# Relay_Board_Rev1-2_-_EasyEDA.net
KiCad netlist of a schematic drawn in EasyEDA
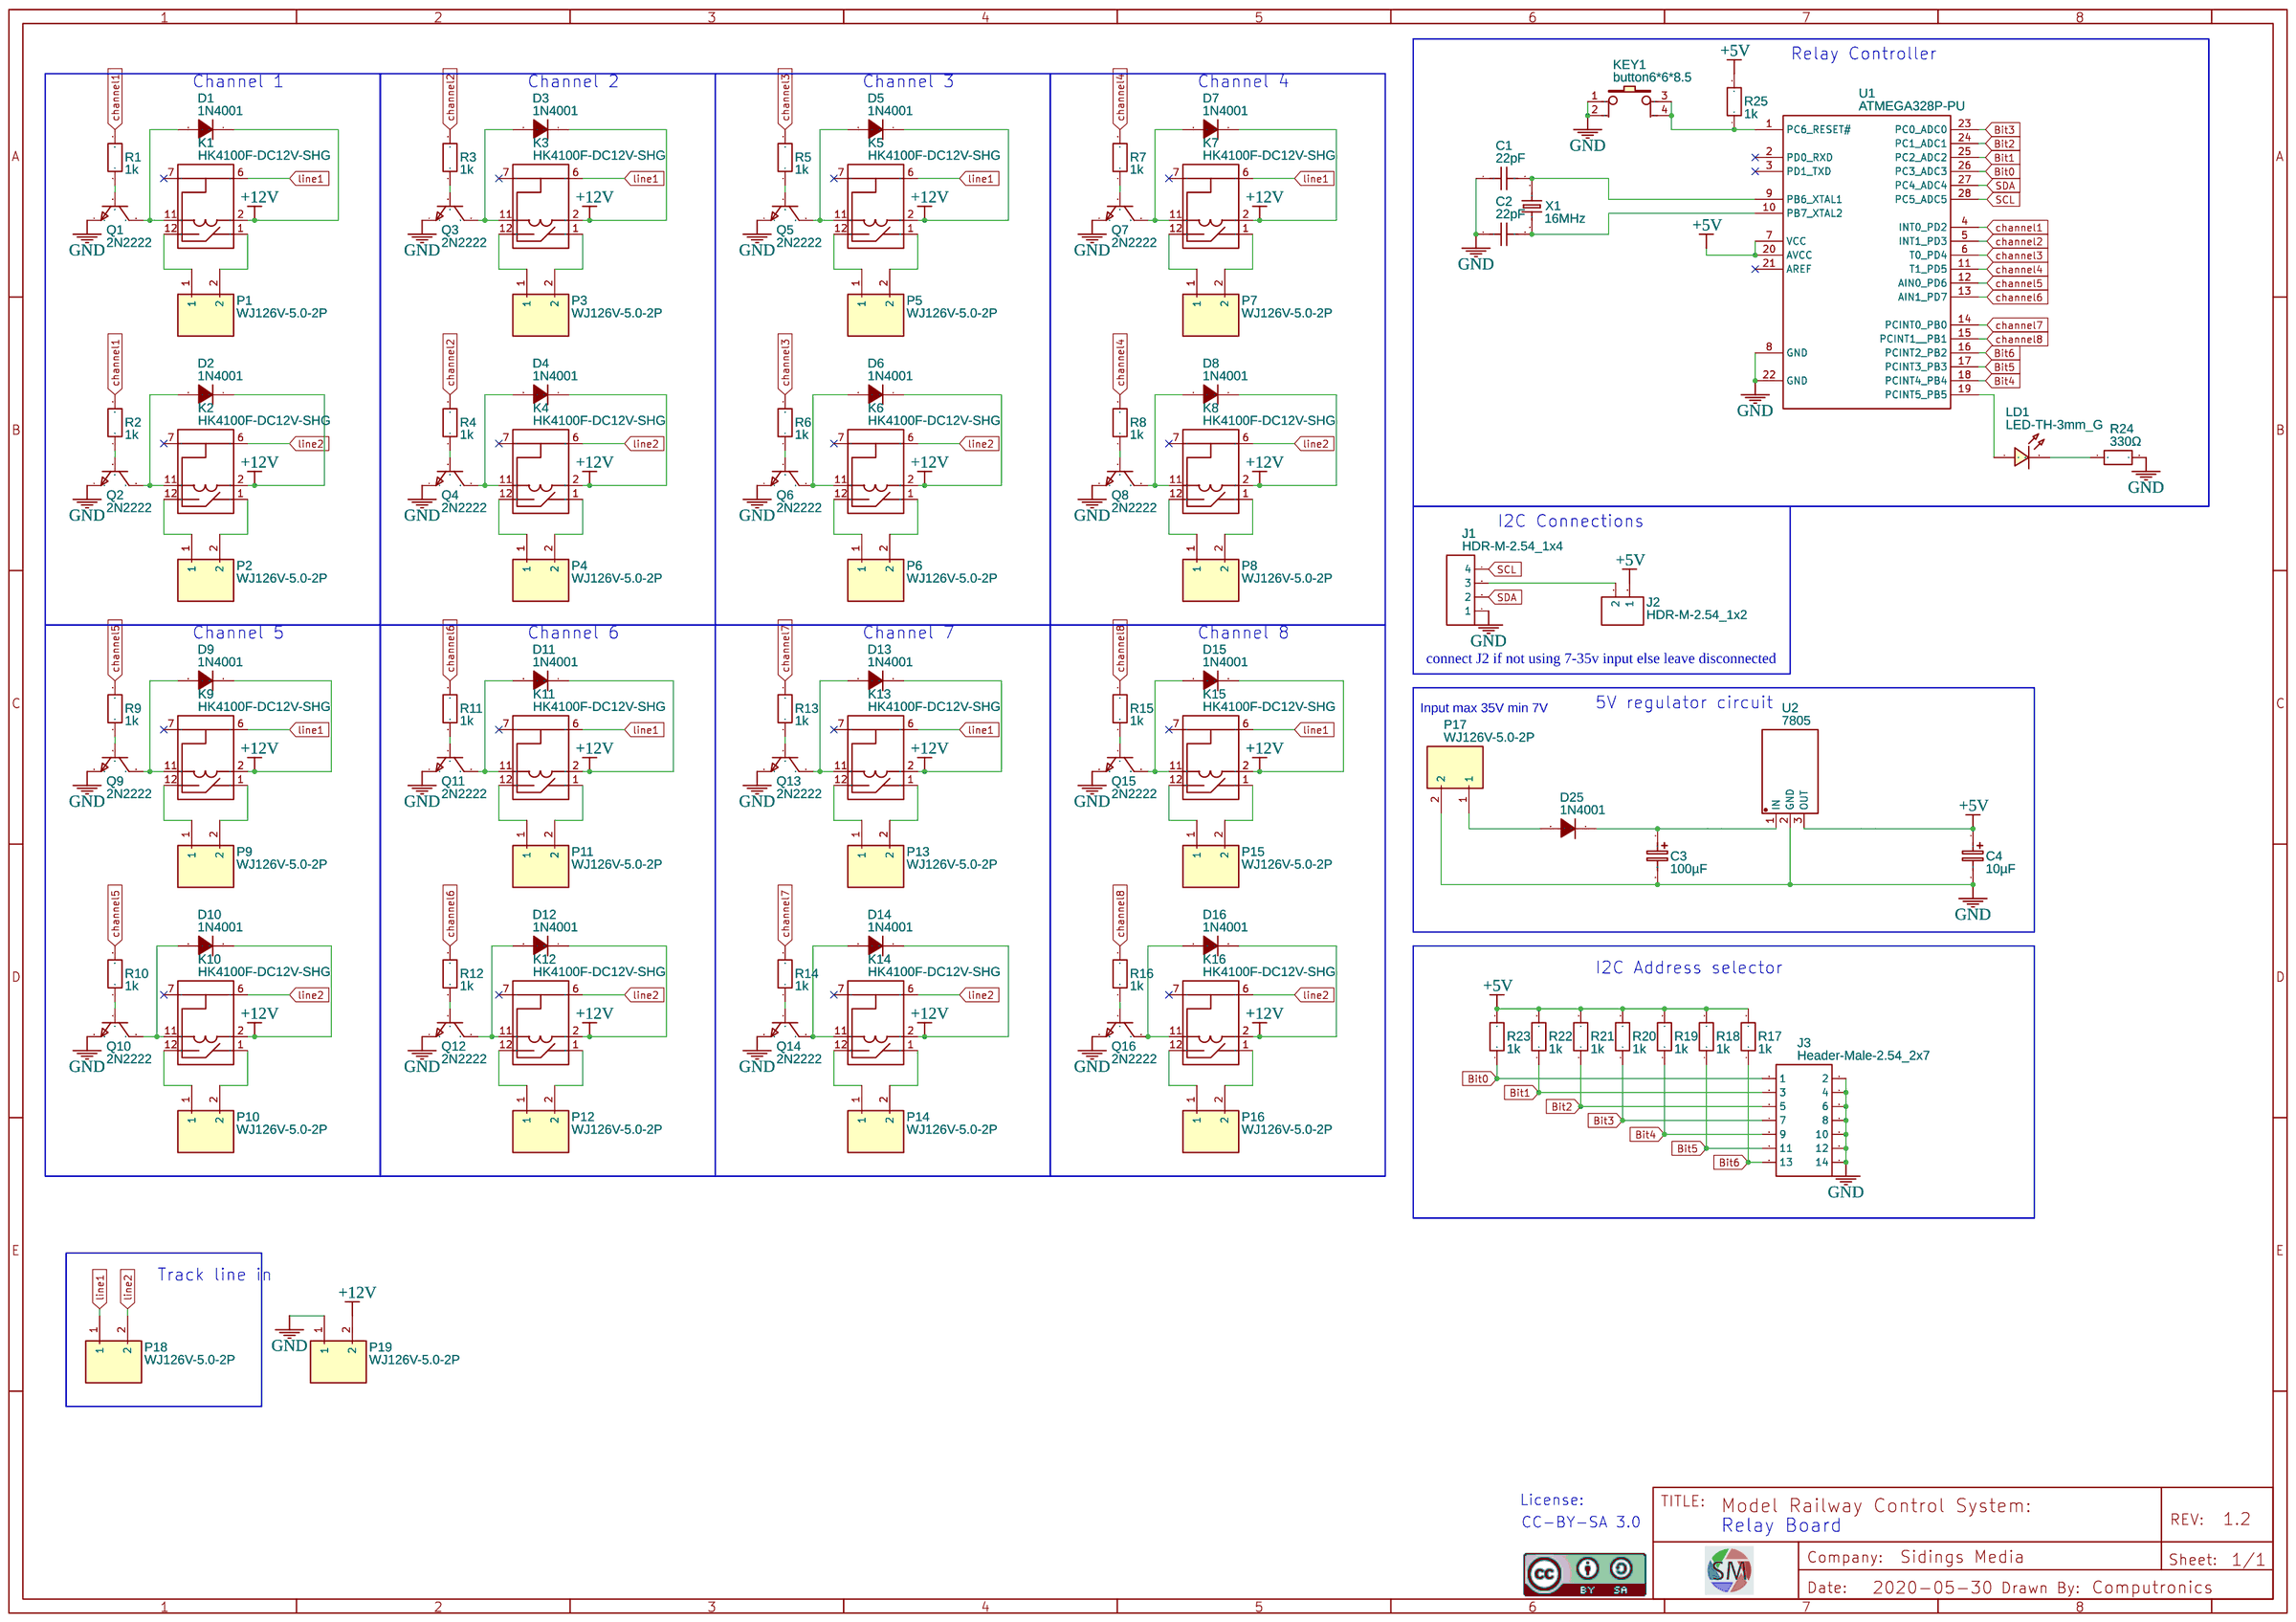
[diagram p0: schematic sheet]

(export (version "E")
  (design (tool "Eeschema 10.0.6"))
  (components
    (comp (ref "C1") (value "22pF") (libsource (lib "") (part "C_RAD-0.2_US")))
    (comp (ref "C2") (value "22pF") (libsource (lib "") (part "C_RAD-0.2_US")))
    (comp (ref "C3") (value "100µF") (libsource (lib "") (part "CE_TH_D3.0×F1.5_EU")))
    (comp (ref "C4") (value "10µF") (libsource (lib "") (part "CE_TH_D3.0×F1.5_EU")))
    (comp (ref "D1")
      (value "1N4001")
      (fields (field (name "BOM_Supplier Part") "C82804"))
      (libsource (lib "") (part "1N4001"))
    )
    (comp (ref "D2")
      (value "1N4001")
      (fields (field (name "BOM_Supplier Part") "C82804"))
      (libsource (lib "") (part "1N4001"))
    )
    (comp (ref "D3")
      (value "1N4001")
      (fields (field (name "BOM_Supplier Part") "C82804"))
      (libsource (lib "") (part "1N4001"))
    )
    (comp (ref "D4")
      (value "1N4001")
      (fields (field (name "BOM_Supplier Part") "C82804"))
      (libsource (lib "") (part "1N4001"))
    )
    (comp (ref "D5")
      (value "1N4001")
      (fields (field (name "BOM_Supplier Part") "C82804"))
      (libsource (lib "") (part "1N4001"))
    )
    (comp (ref "D6")
      (value "1N4001")
      (fields (field (name "BOM_Supplier Part") "C82804"))
      (libsource (lib "") (part "1N4001"))
    )
    (comp (ref "D7")
      (value "1N4001")
      (fields (field (name "BOM_Supplier Part") "C82804"))
      (libsource (lib "") (part "1N4001"))
    )
    (comp (ref "D8")
      (value "1N4001")
      (fields (field (name "BOM_Supplier Part") "C82804"))
      (libsource (lib "") (part "1N4001"))
    )
    (comp (ref "D9")
      (value "1N4001")
      (fields (field (name "BOM_Supplier Part") "C82804"))
      (libsource (lib "") (part "1N4001"))
    )
    (comp (ref "D10")
      (value "1N4001")
      (fields (field (name "BOM_Supplier Part") "C82804"))
      (libsource (lib "") (part "1N4001"))
    )
    (comp (ref "D11")
      (value "1N4001")
      (fields (field (name "BOM_Supplier Part") "C82804"))
      (libsource (lib "") (part "1N4001"))
    )
    (comp (ref "D12")
      (value "1N4001")
      (fields (field (name "BOM_Supplier Part") "C82804"))
      (libsource (lib "") (part "1N4001"))
    )
    (comp (ref "D13")
      (value "1N4001")
      (fields (field (name "BOM_Supplier Part") "C82804"))
      (libsource (lib "") (part "1N4001"))
    )
    (comp (ref "D14")
      (value "1N4001")
      (fields (field (name "BOM_Supplier Part") "C82804"))
      (libsource (lib "") (part "1N4001"))
    )
    (comp (ref "D15")
      (value "1N4001")
      (fields (field (name "BOM_Supplier Part") "C82804"))
      (libsource (lib "") (part "1N4001"))
    )
    (comp (ref "D16")
      (value "1N4001")
      (fields (field (name "BOM_Supplier Part") "C82804"))
      (libsource (lib "") (part "1N4001"))
    )
    (comp (ref "D25")
      (value "1N4001")
      (fields (field (name "BOM_Supplier Part") "C82804"))
      (libsource (lib "") (part "1N4001"))
    )
    (comp (ref "J1")
      (value "HDR-M-2.54_1x4")
      (fields (field (name "BOM_Supplier Part") "C124378"))
      (libsource (lib "") (part "HDR-M-2.54_1x4"))
    )
    (comp (ref "J2")
      (value "HDR-M-2.54_1x2")
      (fields (field (name "BOM_Supplier Part") "C124375"))
      (libsource (lib "") (part "HDR-M-2.54_1x2"))
    )
    (comp (ref "J3")
      (value "Header-Male-2.54_2x7")
      (fields
        (field (name "BOM_Manufacturer Part") "Double row of needle2X7P 2.54mm")
        (field (name "BOM_Supplier Part") "C71397")
      )
      (libsource (lib "") (part "Header-Male-2.54_2x7"))
    )
    (comp (ref "K1")
      (value "HK4100F-DC12V-SHG")
      (fields (field (name "BOM_Supplier Part") "C13467"))
      (libsource (lib "") (part "HK4100F-DC12V-SHG_1"))
    )
    (comp (ref "K2")
      (value "HK4100F-DC12V-SHG")
      (fields (field (name "BOM_Supplier Part") "C13467"))
      (libsource (lib "") (part "HK4100F-DC12V-SHG_1"))
    )
    (comp (ref "K3")
      (value "HK4100F-DC12V-SHG")
      (fields (field (name "BOM_Supplier Part") "C13467"))
      (libsource (lib "") (part "HK4100F-DC12V-SHG"))
    )
    (comp (ref "K4")
      (value "HK4100F-DC12V-SHG")
      (fields (field (name "BOM_Supplier Part") "C13467"))
      (libsource (lib "") (part "HK4100F-DC12V-SHG"))
    )
    (comp (ref "K5")
      (value "HK4100F-DC12V-SHG")
      (fields (field (name "BOM_Supplier Part") "C13467"))
      (libsource (lib "") (part "HK4100F-DC12V-SHG"))
    )
    (comp (ref "K6")
      (value "HK4100F-DC12V-SHG")
      (fields (field (name "BOM_Supplier Part") "C13467"))
      (libsource (lib "") (part "HK4100F-DC12V-SHG"))
    )
    (comp (ref "K7")
      (value "HK4100F-DC12V-SHG")
      (fields (field (name "BOM_Supplier Part") "C13467"))
      (libsource (lib "") (part "HK4100F-DC12V-SHG"))
    )
    (comp (ref "K8")
      (value "HK4100F-DC12V-SHG")
      (fields (field (name "BOM_Supplier Part") "C13467"))
      (libsource (lib "") (part "HK4100F-DC12V-SHG"))
    )
    (comp (ref "K9")
      (value "HK4100F-DC12V-SHG")
      (fields (field (name "BOM_Supplier Part") "C13467"))
      (libsource (lib "") (part "HK4100F-DC12V-SHG_1"))
    )
    (comp (ref "K10")
      (value "HK4100F-DC12V-SHG")
      (fields (field (name "BOM_Supplier Part") "C13467"))
      (libsource (lib "") (part "HK4100F-DC12V-SHG_1"))
    )
    (comp (ref "K11")
      (value "HK4100F-DC12V-SHG")
      (fields (field (name "BOM_Supplier Part") "C13467"))
      (libsource (lib "") (part "HK4100F-DC12V-SHG"))
    )
    (comp (ref "K12")
      (value "HK4100F-DC12V-SHG")
      (fields (field (name "BOM_Supplier Part") "C13467"))
      (libsource (lib "") (part "HK4100F-DC12V-SHG"))
    )
    (comp (ref "K13")
      (value "HK4100F-DC12V-SHG")
      (fields (field (name "BOM_Supplier Part") "C13467"))
      (libsource (lib "") (part "HK4100F-DC12V-SHG"))
    )
    (comp (ref "K14")
      (value "HK4100F-DC12V-SHG")
      (fields (field (name "BOM_Supplier Part") "C13467"))
      (libsource (lib "") (part "HK4100F-DC12V-SHG"))
    )
    (comp (ref "K15")
      (value "HK4100F-DC12V-SHG")
      (fields (field (name "BOM_Supplier Part") "C13467"))
      (libsource (lib "") (part "HK4100F-DC12V-SHG"))
    )
    (comp (ref "K16")
      (value "HK4100F-DC12V-SHG")
      (fields (field (name "BOM_Supplier Part") "C13467"))
      (libsource (lib "") (part "HK4100F-DC12V-SHG"))
    )
    (comp (ref "KEY1")
      (value "button6*6*8.5")
      (fields (field (name "BOM_Supplier Part") "C59980"))
      (libsource (lib "") (part "button6*6*8.5"))
    )
    (comp (ref "LD1")
      (value "LED-TH-3mm_G")
      (fields
        (field (name "BOM_Manufacturer Part") "204-10SYGD/S530-E3")
        (field (name "BOM_Supplier Part") "C85161")
      )
      (libsource (lib "") (part "LED-TH-3mm_G"))
    )
    (comp (ref "P1")
      (value "WJ126V-5.0-2P")
      (fields (field (name "BOM_Supplier Part") "C8404"))
      (libsource (lib "") (part "WJ126V-5.0-2P"))
    )
    (comp (ref "P2")
      (value "WJ126V-5.0-2P")
      (fields (field (name "BOM_Supplier Part") "C8404"))
      (libsource (lib "") (part "WJ126V-5.0-2P"))
    )
    (comp (ref "P3")
      (value "WJ126V-5.0-2P")
      (fields (field (name "BOM_Supplier Part") "C8404"))
      (libsource (lib "") (part "WJ126V-5.0-2P"))
    )
    (comp (ref "P4")
      (value "WJ126V-5.0-2P")
      (fields (field (name "BOM_Supplier Part") "C8404"))
      (libsource (lib "") (part "WJ126V-5.0-2P"))
    )
    (comp (ref "P5")
      (value "WJ126V-5.0-2P")
      (fields (field (name "BOM_Supplier Part") "C8404"))
      (libsource (lib "") (part "WJ126V-5.0-2P"))
    )
    (comp (ref "P6")
      (value "WJ126V-5.0-2P")
      (fields (field (name "BOM_Supplier Part") "C8404"))
      (libsource (lib "") (part "WJ126V-5.0-2P"))
    )
    (comp (ref "P7")
      (value "WJ126V-5.0-2P")
      (fields (field (name "BOM_Supplier Part") "C8404"))
      (libsource (lib "") (part "WJ126V-5.0-2P"))
    )
    (comp (ref "P8")
      (value "WJ126V-5.0-2P")
      (fields (field (name "BOM_Supplier Part") "C8404"))
      (libsource (lib "") (part "WJ126V-5.0-2P"))
    )
    (comp (ref "P9")
      (value "WJ126V-5.0-2P")
      (fields (field (name "BOM_Supplier Part") "C8404"))
      (libsource (lib "") (part "WJ126V-5.0-2P"))
    )
    (comp (ref "P10")
      (value "WJ126V-5.0-2P")
      (fields (field (name "BOM_Supplier Part") "C8404"))
      (libsource (lib "") (part "WJ126V-5.0-2P"))
    )
    (comp (ref "P11")
      (value "WJ126V-5.0-2P")
      (fields (field (name "BOM_Supplier Part") "C8404"))
      (libsource (lib "") (part "WJ126V-5.0-2P"))
    )
    (comp (ref "P12")
      (value "WJ126V-5.0-2P")
      (fields (field (name "BOM_Supplier Part") "C8404"))
      (libsource (lib "") (part "WJ126V-5.0-2P"))
    )
    (comp (ref "P13")
      (value "WJ126V-5.0-2P")
      (fields (field (name "BOM_Supplier Part") "C8404"))
      (libsource (lib "") (part "WJ126V-5.0-2P"))
    )
    (comp (ref "P14")
      (value "WJ126V-5.0-2P")
      (fields (field (name "BOM_Supplier Part") "C8404"))
      (libsource (lib "") (part "WJ126V-5.0-2P"))
    )
    (comp (ref "P15")
      (value "WJ126V-5.0-2P")
      (fields (field (name "BOM_Supplier Part") "C8404"))
      (libsource (lib "") (part "WJ126V-5.0-2P"))
    )
    (comp (ref "P16")
      (value "WJ126V-5.0-2P")
      (fields (field (name "BOM_Supplier Part") "C8404"))
      (libsource (lib "") (part "WJ126V-5.0-2P"))
    )
    (comp (ref "P17")
      (value "WJ126V-5.0-2P")
      (fields (field (name "BOM_Supplier Part") "C8404"))
      (libsource (lib "") (part "WJ126V-5.0-2P_1"))
    )
    (comp (ref "P18")
      (value "WJ126V-5.0-2P")
      (fields (field (name "BOM_Supplier Part") "C8404"))
      (libsource (lib "") (part "WJ126V-5.0-2P"))
    )
    (comp (ref "P19")
      (value "WJ126V-5.0-2P")
      (fields (field (name "BOM_Supplier Part") "C8404"))
      (libsource (lib "") (part "WJ126V-5.0-2P"))
    )
    (comp (ref "Q1")
      (value "2N2222")
      (fields (field (name "BOM_Supplier Part") "C118536"))
      (libsource (lib "") (part "2N2222"))
    )
    (comp (ref "Q2")
      (value "2N2222")
      (fields (field (name "BOM_Supplier Part") "C118536"))
      (libsource (lib "") (part "2N2222"))
    )
    (comp (ref "Q3")
      (value "2N2222")
      (fields (field (name "BOM_Supplier Part") "C118536"))
      (libsource (lib "") (part "2N2222"))
    )
    (comp (ref "Q4")
      (value "2N2222")
      (fields (field (name "BOM_Supplier Part") "C118536"))
      (libsource (lib "") (part "2N2222"))
    )
    (comp (ref "Q5")
      (value "2N2222")
      (fields (field (name "BOM_Supplier Part") "C118536"))
      (libsource (lib "") (part "2N2222"))
    )
    (comp (ref "Q6")
      (value "2N2222")
      (fields (field (name "BOM_Supplier Part") "C118536"))
      (libsource (lib "") (part "2N2222"))
    )
    (comp (ref "Q7")
      (value "2N2222")
      (fields (field (name "BOM_Supplier Part") "C118536"))
      (libsource (lib "") (part "2N2222"))
    )
    (comp (ref "Q8")
      (value "2N2222")
      (fields (field (name "BOM_Supplier Part") "C118536"))
      (libsource (lib "") (part "2N2222"))
    )
    (comp (ref "Q9")
      (value "2N2222")
      (fields (field (name "BOM_Supplier Part") "C118536"))
      (libsource (lib "") (part "2N2222"))
    )
    (comp (ref "Q10")
      (value "2N2222")
      (fields (field (name "BOM_Supplier Part") "C118536"))
      (libsource (lib "") (part "2N2222"))
    )
    (comp (ref "Q11")
      (value "2N2222")
      (fields (field (name "BOM_Supplier Part") "C118536"))
      (libsource (lib "") (part "2N2222"))
    )
    (comp (ref "Q12")
      (value "2N2222")
      (fields (field (name "BOM_Supplier Part") "C118536"))
      (libsource (lib "") (part "2N2222"))
    )
    (comp (ref "Q13")
      (value "2N2222")
      (fields (field (name "BOM_Supplier Part") "C118536"))
      (libsource (lib "") (part "2N2222"))
    )
    (comp (ref "Q14")
      (value "2N2222")
      (fields (field (name "BOM_Supplier Part") "C118536"))
      (libsource (lib "") (part "2N2222"))
    )
    (comp (ref "Q15")
      (value "2N2222")
      (fields (field (name "BOM_Supplier Part") "C118536"))
      (libsource (lib "") (part "2N2222"))
    )
    (comp (ref "Q16")
      (value "2N2222")
      (fields (field (name "BOM_Supplier Part") "C118536"))
      (libsource (lib "") (part "2N2222"))
    )
    (comp (ref "R1") (value "1k") (libsource (lib "") (part "R_AXIAL-0.4_EU")))
    (comp (ref "R2") (value "1k") (libsource (lib "") (part "R_AXIAL-0.4_EU")))
    (comp (ref "R3") (value "1k") (libsource (lib "") (part "R_AXIAL-0.4_EU")))
    (comp (ref "R4") (value "1k") (libsource (lib "") (part "R_AXIAL-0.4_EU")))
    (comp (ref "R5") (value "1k") (libsource (lib "") (part "R_AXIAL-0.4_EU")))
    (comp (ref "R6") (value "1k") (libsource (lib "") (part "R_AXIAL-0.4_EU")))
    (comp (ref "R7") (value "1k") (libsource (lib "") (part "R_AXIAL-0.4_EU")))
    (comp (ref "R8") (value "1k") (libsource (lib "") (part "R_AXIAL-0.4_EU")))
    (comp (ref "R9") (value "1k") (libsource (lib "") (part "R_AXIAL-0.4_EU")))
    (comp (ref "R10") (value "1k") (libsource (lib "") (part "R_AXIAL-0.4_EU")))
    (comp (ref "R11") (value "1k") (libsource (lib "") (part "R_AXIAL-0.4_EU")))
    (comp (ref "R12") (value "1k") (libsource (lib "") (part "R_AXIAL-0.4_EU")))
    (comp (ref "R13") (value "1k") (libsource (lib "") (part "R_AXIAL-0.4_EU")))
    (comp (ref "R14") (value "1k") (libsource (lib "") (part "R_AXIAL-0.4_EU")))
    (comp (ref "R15") (value "1k") (libsource (lib "") (part "R_AXIAL-0.4_EU")))
    (comp (ref "R16") (value "1k") (libsource (lib "") (part "R_AXIAL-0.4_EU")))
    (comp (ref "R17") (value "1k") (libsource (lib "") (part "R_AXIAL-0.4_EU")))
    (comp (ref "R18") (value "1k") (libsource (lib "") (part "R_AXIAL-0.4_EU")))
    (comp (ref "R19") (value "1k") (libsource (lib "") (part "R_AXIAL-0.4_EU")))
    (comp (ref "R20") (value "1k") (libsource (lib "") (part "R_AXIAL-0.4_EU")))
    (comp (ref "R21") (value "1k") (libsource (lib "") (part "R_AXIAL-0.4_EU")))
    (comp (ref "R22") (value "1k") (libsource (lib "") (part "R_AXIAL-0.4_EU")))
    (comp (ref "R23") (value "1k") (libsource (lib "") (part "R_AXIAL-0.4_EU")))
    (comp (ref "R24") (value "330Ω") (libsource (lib "") (part "R_AXIAL-0.4_EU_1")))
    (comp (ref "R25") (value "1k") (libsource (lib "") (part "R_AXIAL-0.4_EU")))
    (comp (ref "U1")
      (value "ATMEGA328P-PU")
      (fields (field (name "BOM_Supplier Part") "C33901"))
      (libsource (lib "") (part "ATMEGA328P-PU"))
    )
    (comp (ref "U2")
      (value "7805")
      (fields (field (name "BOM_Supplier Part") "C305416"))
      (libsource (lib "") (part "7805"))
    )
    (comp (ref "X1")
      (value "16MHz")
      (fields
        (field (name "BOM_Manufacturer Part") "XIHCELNANF-16MHZ")
        (field (name "BOM_Supplier Part") "C295075")
      )
      (libsource (lib "") (part "XIHCELNANF-16MHZ"))
    )
  )
  (nets
    (net (code "1") (name "+5V") (class "Default")
      (node (ref "C4") (pin "1") (pinfunction "1_1") (pintype "unspecified"))
      (node (ref "J2") (pin "1") (pinfunction "1_1") (pintype "unspecified"))
      (node (ref "R17") (pin "2") (pinfunction "2_2") (pintype "unspecified"))
      (node (ref "R18") (pin "2") (pinfunction "2_2") (pintype "unspecified"))
      (node (ref "R19") (pin "2") (pinfunction "2_2") (pintype "unspecified"))
      (node (ref "R20") (pin "2") (pinfunction "2_2") (pintype "unspecified"))
      (node (ref "R21") (pin "2") (pinfunction "2_2") (pintype "unspecified"))
      (node (ref "R22") (pin "2") (pinfunction "2_2") (pintype "unspecified"))
      (node (ref "R23") (pin "2") (pinfunction "2_2") (pintype "unspecified"))
      (node (ref "R25") (pin "2") (pinfunction "2_2") (pintype "unspecified"))
      (node (ref "U1") (pin "20") (pinfunction "AVCC_20") (pintype "passive"))
      (node (ref "U1") (pin "7") (pinfunction "VCC_7") (pintype "passive"))
      (node (ref "U2") (pin "3") (pinfunction "OUT_3") (pintype "unspecified"))
    )
    (net (code "2") (name "+12V") (class "Default")
      (node (ref "D1") (pin "1") (pinfunction "K_1") (pintype "unspecified"))
      (node (ref "D10") (pin "1") (pinfunction "K_1") (pintype "unspecified"))
      (node (ref "D11") (pin "1") (pinfunction "K_1") (pintype "unspecified"))
      (node (ref "D12") (pin "1") (pinfunction "K_1") (pintype "unspecified"))
      (node (ref "D13") (pin "1") (pinfunction "K_1") (pintype "unspecified"))
      (node (ref "D14") (pin "1") (pinfunction "K_1") (pintype "unspecified"))
      (node (ref "D15") (pin "1") (pinfunction "K_1") (pintype "unspecified"))
      (node (ref "D16") (pin "1") (pinfunction "K_1") (pintype "unspecified"))
      (node (ref "D2") (pin "1") (pinfunction "K_1") (pintype "unspecified"))
      (node (ref "D3") (pin "1") (pinfunction "K_1") (pintype "unspecified"))
      (node (ref "D4") (pin "1") (pinfunction "K_1") (pintype "unspecified"))
      (node (ref "D5") (pin "1") (pinfunction "K_1") (pintype "unspecified"))
      (node (ref "D6") (pin "1") (pinfunction "K_1") (pintype "unspecified"))
      (node (ref "D7") (pin "1") (pinfunction "K_1") (pintype "unspecified"))
      (node (ref "D8") (pin "1") (pinfunction "K_1") (pintype "unspecified"))
      (node (ref "D9") (pin "1") (pinfunction "K_1") (pintype "unspecified"))
      (node (ref "K1") (pin "2") (pinfunction "2_2") (pintype "unspecified"))
      (node (ref "K10") (pin "2") (pinfunction "2_2") (pintype "unspecified"))
      (node (ref "K11") (pin "2") (pinfunction "2_2") (pintype "unspecified"))
      (node (ref "K12") (pin "2") (pinfunction "2_2") (pintype "unspecified"))
      (node (ref "K13") (pin "2") (pinfunction "2_2") (pintype "unspecified"))
      (node (ref "K14") (pin "2") (pinfunction "2_2") (pintype "unspecified"))
      (node (ref "K15") (pin "2") (pinfunction "2_2") (pintype "unspecified"))
      (node (ref "K16") (pin "2") (pinfunction "2_2") (pintype "unspecified"))
      (node (ref "K2") (pin "2") (pinfunction "2_2") (pintype "unspecified"))
      (node (ref "K3") (pin "2") (pinfunction "2_2") (pintype "unspecified"))
      (node (ref "K4") (pin "2") (pinfunction "2_2") (pintype "unspecified"))
      (node (ref "K5") (pin "2") (pinfunction "2_2") (pintype "unspecified"))
      (node (ref "K6") (pin "2") (pinfunction "2_2") (pintype "unspecified"))
      (node (ref "K7") (pin "2") (pinfunction "2_2") (pintype "unspecified"))
      (node (ref "K8") (pin "2") (pinfunction "2_2") (pintype "unspecified"))
      (node (ref "K9") (pin "2") (pinfunction "2_2") (pintype "unspecified"))
      (node (ref "P19") (pin "2") (pinfunction "2_2") (pintype "input"))
    )
    (net (code "3") (name "Bit0") (class "Default")
      (node (ref "J3") (pin "1") (pinfunction "1_1") (pintype "input"))
      (node (ref "R23") (pin "1") (pinfunction "1_1") (pintype "unspecified"))
      (node (ref "U1") (pin "26") (pinfunction "PC3_ADC3_26") (pintype "bidirectional"))
    )
    (net (code "4") (name "Bit1") (class "Default")
      (node (ref "J3") (pin "3") (pinfunction "3_3") (pintype "input"))
      (node (ref "R22") (pin "1") (pinfunction "1_1") (pintype "unspecified"))
      (node (ref "U1") (pin "25") (pinfunction "PC2_ADC2_25") (pintype "bidirectional"))
    )
    (net (code "5") (name "Bit2") (class "Default")
      (node (ref "J3") (pin "5") (pinfunction "5_5") (pintype "input"))
      (node (ref "R21") (pin "1") (pinfunction "1_1") (pintype "unspecified"))
      (node (ref "U1") (pin "24") (pinfunction "PC1_ADC1_24") (pintype "bidirectional"))
    )
    (net (code "6") (name "Bit3") (class "Default")
      (node (ref "J3") (pin "7") (pinfunction "7_7") (pintype "input"))
      (node (ref "R20") (pin "1") (pinfunction "1_1") (pintype "unspecified"))
      (node (ref "U1") (pin "23") (pinfunction "PC0_ADC0_23") (pintype "bidirectional"))
    )
    (net (code "7") (name "Bit4") (class "Default")
      (node (ref "J3") (pin "9") (pinfunction "9_9") (pintype "input"))
      (node (ref "R19") (pin "1") (pinfunction "1_1") (pintype "unspecified"))
      (node (ref "U1") (pin "18") (pinfunction "PCINT4_PB4_18") (pintype "bidirectional"))
    )
    (net (code "8") (name "Bit5") (class "Default")
      (node (ref "J3") (pin "11") (pinfunction "11_11") (pintype "input"))
      (node (ref "R18") (pin "1") (pinfunction "1_1") (pintype "unspecified"))
      (node (ref "U1") (pin "17") (pinfunction "PCINT3_PB3_17") (pintype "bidirectional"))
    )
    (net (code "9") (name "Bit6") (class "Default")
      (node (ref "J3") (pin "13") (pinfunction "13_13") (pintype "input"))
      (node (ref "R17") (pin "1") (pinfunction "1_1") (pintype "unspecified"))
      (node (ref "U1") (pin "16") (pinfunction "PCINT2_PB2_16") (pintype "bidirectional"))
    )
    (net (code "10") (name "GND") (class "Default")
      (node (ref "C1") (pin "1") (pinfunction "1_1") (pintype "unspecified"))
      (node (ref "C2") (pin "1") (pinfunction "1_1") (pintype "unspecified"))
      (node (ref "C3") (pin "2") (pinfunction "2_2") (pintype "unspecified"))
      (node (ref "C4") (pin "2") (pinfunction "2_2") (pintype "unspecified"))
      (node (ref "J1") (pin "1") (pinfunction "1_1") (pintype "unspecified"))
      (node (ref "J3") (pin "10") (pinfunction "10_10") (pintype "input"))
      (node (ref "J3") (pin "12") (pinfunction "12_12") (pintype "input"))
      (node (ref "J3") (pin "14") (pinfunction "14_14") (pintype "input"))
      (node (ref "J3") (pin "2") (pinfunction "2_2") (pintype "input"))
      (node (ref "J3") (pin "4") (pinfunction "4_4") (pintype "input"))
      (node (ref "J3") (pin "6") (pinfunction "6_6") (pintype "input"))
      (node (ref "J3") (pin "8") (pinfunction "8_8") (pintype "input"))
      (node (ref "KEY1") (pin "1") (pinfunction "1_1") (pintype "input"))
      (node (ref "KEY1") (pin "2") (pinfunction "2_2") (pintype "input"))
      (node (ref "P17") (pin "2") (pinfunction "2_2") (pintype "input"))
      (node (ref "P19") (pin "1") (pinfunction "1_1") (pintype "input"))
      (node (ref "Q1") (pin "1") (pinfunction "E_1") (pintype "unspecified"))
      (node (ref "Q10") (pin "1") (pinfunction "E_1") (pintype "unspecified"))
      (node (ref "Q11") (pin "1") (pinfunction "E_1") (pintype "unspecified"))
      (node (ref "Q12") (pin "1") (pinfunction "E_1") (pintype "unspecified"))
      (node (ref "Q13") (pin "1") (pinfunction "E_1") (pintype "unspecified"))
      (node (ref "Q14") (pin "1") (pinfunction "E_1") (pintype "unspecified"))
      (node (ref "Q15") (pin "1") (pinfunction "E_1") (pintype "unspecified"))
      (node (ref "Q16") (pin "1") (pinfunction "E_1") (pintype "unspecified"))
      (node (ref "Q2") (pin "1") (pinfunction "E_1") (pintype "unspecified"))
      (node (ref "Q3") (pin "1") (pinfunction "E_1") (pintype "unspecified"))
      (node (ref "Q4") (pin "1") (pinfunction "E_1") (pintype "unspecified"))
      (node (ref "Q5") (pin "1") (pinfunction "E_1") (pintype "unspecified"))
      (node (ref "Q6") (pin "1") (pinfunction "E_1") (pintype "unspecified"))
      (node (ref "Q7") (pin "1") (pinfunction "E_1") (pintype "unspecified"))
      (node (ref "Q8") (pin "1") (pinfunction "E_1") (pintype "unspecified"))
      (node (ref "Q9") (pin "1") (pinfunction "E_1") (pintype "unspecified"))
      (node (ref "R24") (pin "2") (pinfunction "2_2") (pintype "unspecified"))
      (node (ref "U1") (pin "22") (pinfunction "GND_22") (pintype "passive"))
      (node (ref "U1") (pin "8") (pinfunction "GND_8") (pintype "passive"))
      (node (ref "U2") (pin "2") (pinfunction "GND_2") (pintype "unspecified"))
    )
    (net (code "11") (name "Net-(D1-A)") (class "Default")
      (node (ref "D1") (pin "2") (pinfunction "A_2") (pintype "unspecified"))
      (node (ref "K1") (pin "11") (pinfunction "11_11") (pintype "unspecified"))
      (node (ref "Q1") (pin "3") (pinfunction "C_3") (pintype "unspecified"))
    )
    (net (code "12") (name "Net-(D2-A)") (class "Default")
      (node (ref "D2") (pin "2") (pinfunction "A_2") (pintype "unspecified"))
      (node (ref "K2") (pin "11") (pinfunction "11_11") (pintype "unspecified"))
      (node (ref "Q2") (pin "3") (pinfunction "C_3") (pintype "unspecified"))
    )
    (net (code "13") (name "Net-(D3-A)") (class "Default")
      (node (ref "D3") (pin "2") (pinfunction "A_2") (pintype "unspecified"))
      (node (ref "K3") (pin "11") (pinfunction "11_11") (pintype "unspecified"))
      (node (ref "Q3") (pin "3") (pinfunction "C_3") (pintype "unspecified"))
    )
    (net (code "14") (name "Net-(D4-A)") (class "Default")
      (node (ref "D4") (pin "2") (pinfunction "A_2") (pintype "unspecified"))
      (node (ref "K4") (pin "11") (pinfunction "11_11") (pintype "unspecified"))
      (node (ref "Q4") (pin "3") (pinfunction "C_3") (pintype "unspecified"))
    )
    (net (code "15") (name "Net-(D5-A)") (class "Default")
      (node (ref "D5") (pin "2") (pinfunction "A_2") (pintype "unspecified"))
      (node (ref "K5") (pin "11") (pinfunction "11_11") (pintype "unspecified"))
      (node (ref "Q5") (pin "3") (pinfunction "C_3") (pintype "unspecified"))
    )
    (net (code "16") (name "Net-(D6-A)") (class "Default")
      (node (ref "D6") (pin "2") (pinfunction "A_2") (pintype "unspecified"))
      (node (ref "K6") (pin "11") (pinfunction "11_11") (pintype "unspecified"))
      (node (ref "Q6") (pin "3") (pinfunction "C_3") (pintype "unspecified"))
    )
    (net (code "17") (name "Net-(D7-A)") (class "Default")
      (node (ref "D7") (pin "2") (pinfunction "A_2") (pintype "unspecified"))
      (node (ref "K7") (pin "11") (pinfunction "11_11") (pintype "unspecified"))
      (node (ref "Q7") (pin "3") (pinfunction "C_3") (pintype "unspecified"))
    )
    (net (code "18") (name "Net-(D8-A)") (class "Default")
      (node (ref "D8") (pin "2") (pinfunction "A_2") (pintype "unspecified"))
      (node (ref "K8") (pin "11") (pinfunction "11_11") (pintype "unspecified"))
      (node (ref "Q8") (pin "3") (pinfunction "C_3") (pintype "unspecified"))
    )
    (net (code "19") (name "Net-(D9-A)") (class "Default")
      (node (ref "D9") (pin "2") (pinfunction "A_2") (pintype "unspecified"))
      (node (ref "K9") (pin "11") (pinfunction "11_11") (pintype "unspecified"))
      (node (ref "Q9") (pin "3") (pinfunction "C_3") (pintype "unspecified"))
    )
    (net (code "20") (name "Net-(D10-A)") (class "Default")
      (node (ref "D10") (pin "2") (pinfunction "A_2") (pintype "unspecified"))
      (node (ref "K10") (pin "11") (pinfunction "11_11") (pintype "unspecified"))
      (node (ref "Q10") (pin "3") (pinfunction "C_3") (pintype "unspecified"))
    )
    (net (code "21") (name "Net-(D11-A)") (class "Default")
      (node (ref "D11") (pin "2") (pinfunction "A_2") (pintype "unspecified"))
      (node (ref "K11") (pin "11") (pinfunction "11_11") (pintype "unspecified"))
      (node (ref "Q11") (pin "3") (pinfunction "C_3") (pintype "unspecified"))
    )
    (net (code "22") (name "Net-(D12-A)") (class "Default")
      (node (ref "D12") (pin "2") (pinfunction "A_2") (pintype "unspecified"))
      (node (ref "K12") (pin "11") (pinfunction "11_11") (pintype "unspecified"))
      (node (ref "Q12") (pin "3") (pinfunction "C_3") (pintype "unspecified"))
    )
    (net (code "23") (name "Net-(D13-A)") (class "Default")
      (node (ref "D13") (pin "2") (pinfunction "A_2") (pintype "unspecified"))
      (node (ref "K13") (pin "11") (pinfunction "11_11") (pintype "unspecified"))
      (node (ref "Q13") (pin "3") (pinfunction "C_3") (pintype "unspecified"))
    )
    (net (code "24") (name "Net-(D14-A)") (class "Default")
      (node (ref "D14") (pin "2") (pinfunction "A_2") (pintype "unspecified"))
      (node (ref "K14") (pin "11") (pinfunction "11_11") (pintype "unspecified"))
      (node (ref "Q14") (pin "3") (pinfunction "C_3") (pintype "unspecified"))
    )
    (net (code "25") (name "Net-(D15-A)") (class "Default")
      (node (ref "D15") (pin "2") (pinfunction "A_2") (pintype "unspecified"))
      (node (ref "K15") (pin "11") (pinfunction "11_11") (pintype "unspecified"))
      (node (ref "Q15") (pin "3") (pinfunction "C_3") (pintype "unspecified"))
    )
    (net (code "26") (name "Net-(D16-A)") (class "Default")
      (node (ref "D16") (pin "2") (pinfunction "A_2") (pintype "unspecified"))
      (node (ref "K16") (pin "11") (pinfunction "11_11") (pintype "unspecified"))
      (node (ref "Q16") (pin "3") (pinfunction "C_3") (pintype "unspecified"))
    )
    (net (code "27") (name "Net-(D25-A)") (class "Default")
      (node (ref "D25") (pin "2") (pinfunction "A_2") (pintype "unspecified"))
      (node (ref "P17") (pin "1") (pinfunction "1_1") (pintype "input"))
    )
    (net (code "28") (name "Net-(D25-K)") (class "Default")
      (node (ref "C3") (pin "1") (pinfunction "1_1") (pintype "unspecified"))
      (node (ref "D25") (pin "1") (pinfunction "K_1") (pintype "unspecified"))
      (node (ref "U2") (pin "1") (pinfunction "IN_1") (pintype "unspecified"))
    )
    (net (code "29") (name "Net-(J1-Pad3)") (class "Default")
      (node (ref "J1") (pin "3") (pinfunction "3_3") (pintype "unspecified"))
      (node (ref "J2") (pin "2") (pinfunction "2_2") (pintype "unspecified"))
    )
    (net (code "30") (name "Net-(K1-Pad1)") (class "Default")
      (node (ref "K1") (pin "1") (pinfunction "1_1") (pintype "unspecified"))
      (node (ref "P1") (pin "2") (pinfunction "2_2") (pintype "input"))
    )
    (net (code "31") (name "Net-(K1-Pad12)") (class "Default")
      (node (ref "K1") (pin "12") (pinfunction "12_12") (pintype "unspecified"))
      (node (ref "P1") (pin "1") (pinfunction "1_1") (pintype "input"))
    )
    (net (code "32") (name "Net-(K2-Pad1)") (class "Default")
      (node (ref "K2") (pin "1") (pinfunction "1_1") (pintype "unspecified"))
      (node (ref "P2") (pin "2") (pinfunction "2_2") (pintype "input"))
    )
    (net (code "33") (name "Net-(K2-Pad12)") (class "Default")
      (node (ref "K2") (pin "12") (pinfunction "12_12") (pintype "unspecified"))
      (node (ref "P2") (pin "1") (pinfunction "1_1") (pintype "input"))
    )
    (net (code "34") (name "Net-(K3-Pad1)") (class "Default")
      (node (ref "K3") (pin "1") (pinfunction "1_1") (pintype "unspecified"))
      (node (ref "P3") (pin "2") (pinfunction "2_2") (pintype "input"))
    )
    (net (code "35") (name "Net-(K3-Pad12)") (class "Default")
      (node (ref "K3") (pin "12") (pinfunction "12_12") (pintype "unspecified"))
      (node (ref "P3") (pin "1") (pinfunction "1_1") (pintype "input"))
    )
    (net (code "36") (name "Net-(K4-Pad1)") (class "Default")
      (node (ref "K4") (pin "1") (pinfunction "1_1") (pintype "unspecified"))
      (node (ref "P4") (pin "2") (pinfunction "2_2") (pintype "input"))
    )
    (net (code "37") (name "Net-(K4-Pad12)") (class "Default")
      (node (ref "K4") (pin "12") (pinfunction "12_12") (pintype "unspecified"))
      (node (ref "P4") (pin "1") (pinfunction "1_1") (pintype "input"))
    )
    (net (code "38") (name "Net-(K5-Pad1)") (class "Default")
      (node (ref "K5") (pin "1") (pinfunction "1_1") (pintype "unspecified"))
      (node (ref "P5") (pin "2") (pinfunction "2_2") (pintype "input"))
    )
    (net (code "39") (name "Net-(K5-Pad12)") (class "Default")
      (node (ref "K5") (pin "12") (pinfunction "12_12") (pintype "unspecified"))
      (node (ref "P5") (pin "1") (pinfunction "1_1") (pintype "input"))
    )
    (net (code "40") (name "Net-(K6-Pad1)") (class "Default")
      (node (ref "K6") (pin "1") (pinfunction "1_1") (pintype "unspecified"))
      (node (ref "P6") (pin "2") (pinfunction "2_2") (pintype "input"))
    )
    (net (code "41") (name "Net-(K6-Pad12)") (class "Default")
      (node (ref "K6") (pin "12") (pinfunction "12_12") (pintype "unspecified"))
      (node (ref "P6") (pin "1") (pinfunction "1_1") (pintype "input"))
    )
    (net (code "42") (name "Net-(K7-Pad1)") (class "Default")
      (node (ref "K7") (pin "1") (pinfunction "1_1") (pintype "unspecified"))
      (node (ref "P7") (pin "2") (pinfunction "2_2") (pintype "input"))
    )
    (net (code "43") (name "Net-(K7-Pad12)") (class "Default")
      (node (ref "K7") (pin "12") (pinfunction "12_12") (pintype "unspecified"))
      (node (ref "P7") (pin "1") (pinfunction "1_1") (pintype "input"))
    )
    (net (code "44") (name "Net-(K8-Pad1)") (class "Default")
      (node (ref "K8") (pin "1") (pinfunction "1_1") (pintype "unspecified"))
      (node (ref "P8") (pin "2") (pinfunction "2_2") (pintype "input"))
    )
    (net (code "45") (name "Net-(K8-Pad12)") (class "Default")
      (node (ref "K8") (pin "12") (pinfunction "12_12") (pintype "unspecified"))
      (node (ref "P8") (pin "1") (pinfunction "1_1") (pintype "input"))
    )
    (net (code "46") (name "Net-(K9-Pad1)") (class "Default")
      (node (ref "K9") (pin "1") (pinfunction "1_1") (pintype "unspecified"))
      (node (ref "P9") (pin "2") (pinfunction "2_2") (pintype "input"))
    )
    (net (code "47") (name "Net-(K9-Pad12)") (class "Default")
      (node (ref "K9") (pin "12") (pinfunction "12_12") (pintype "unspecified"))
      (node (ref "P9") (pin "1") (pinfunction "1_1") (pintype "input"))
    )
    (net (code "48") (name "Net-(K10-Pad1)") (class "Default")
      (node (ref "K10") (pin "1") (pinfunction "1_1") (pintype "unspecified"))
      (node (ref "P10") (pin "2") (pinfunction "2_2") (pintype "input"))
    )
    (net (code "49") (name "Net-(K10-Pad12)") (class "Default")
      (node (ref "K10") (pin "12") (pinfunction "12_12") (pintype "unspecified"))
      (node (ref "P10") (pin "1") (pinfunction "1_1") (pintype "input"))
    )
    (net (code "50") (name "Net-(K11-Pad1)") (class "Default")
      (node (ref "K11") (pin "1") (pinfunction "1_1") (pintype "unspecified"))
      (node (ref "P11") (pin "2") (pinfunction "2_2") (pintype "input"))
    )
    (net (code "51") (name "Net-(K11-Pad12)") (class "Default")
      (node (ref "K11") (pin "12") (pinfunction "12_12") (pintype "unspecified"))
      (node (ref "P11") (pin "1") (pinfunction "1_1") (pintype "input"))
    )
    (net (code "52") (name "Net-(K12-Pad1)") (class "Default")
      (node (ref "K12") (pin "1") (pinfunction "1_1") (pintype "unspecified"))
      (node (ref "P12") (pin "2") (pinfunction "2_2") (pintype "input"))
    )
    (net (code "53") (name "Net-(K12-Pad12)") (class "Default")
      (node (ref "K12") (pin "12") (pinfunction "12_12") (pintype "unspecified"))
      (node (ref "P12") (pin "1") (pinfunction "1_1") (pintype "input"))
    )
    (net (code "54") (name "Net-(K13-Pad1)") (class "Default")
      (node (ref "K13") (pin "1") (pinfunction "1_1") (pintype "unspecified"))
      (node (ref "P13") (pin "2") (pinfunction "2_2") (pintype "input"))
    )
    (net (code "55") (name "Net-(K13-Pad12)") (class "Default")
      (node (ref "K13") (pin "12") (pinfunction "12_12") (pintype "unspecified"))
      (node (ref "P13") (pin "1") (pinfunction "1_1") (pintype "input"))
    )
    (net (code "56") (name "Net-(K14-Pad1)") (class "Default")
      (node (ref "K14") (pin "1") (pinfunction "1_1") (pintype "unspecified"))
      (node (ref "P14") (pin "2") (pinfunction "2_2") (pintype "input"))
    )
    (net (code "57") (name "Net-(K14-Pad12)") (class "Default")
      (node (ref "K14") (pin "12") (pinfunction "12_12") (pintype "unspecified"))
      (node (ref "P14") (pin "1") (pinfunction "1_1") (pintype "input"))
    )
    (net (code "58") (name "Net-(K15-Pad1)") (class "Default")
      (node (ref "K15") (pin "1") (pinfunction "1_1") (pintype "unspecified"))
      (node (ref "P15") (pin "2") (pinfunction "2_2") (pintype "input"))
    )
    (net (code "59") (name "Net-(K15-Pad12)") (class "Default")
      (node (ref "K15") (pin "12") (pinfunction "12_12") (pintype "unspecified"))
      (node (ref "P15") (pin "1") (pinfunction "1_1") (pintype "input"))
    )
    (net (code "60") (name "Net-(K16-Pad1)") (class "Default")
      (node (ref "K16") (pin "1") (pinfunction "1_1") (pintype "unspecified"))
      (node (ref "P16") (pin "2") (pinfunction "2_2") (pintype "input"))
    )
    (net (code "61") (name "Net-(K16-Pad12)") (class "Default")
      (node (ref "K16") (pin "12") (pinfunction "12_12") (pintype "unspecified"))
      (node (ref "P16") (pin "1") (pinfunction "1_1") (pintype "input"))
    )
    (net (code "62") (name "Net-(LD1-Pad2)") (class "Default")
      (node (ref "LD1") (pin "2") (pinfunction "2_2") (pintype "unspecified"))
      (node (ref "R24") (pin "1") (pinfunction "1_1") (pintype "unspecified"))
    )
    (net (code "63") (name "Net-(Q1-B)") (class "Default")
      (node (ref "Q1") (pin "2") (pinfunction "B_2") (pintype "unspecified"))
      (node (ref "R1") (pin "1") (pinfunction "1_1") (pintype "unspecified"))
    )
    (net (code "64") (name "Net-(Q2-B)") (class "Default")
      (node (ref "Q2") (pin "2") (pinfunction "B_2") (pintype "unspecified"))
      (node (ref "R2") (pin "1") (pinfunction "1_1") (pintype "unspecified"))
    )
    (net (code "65") (name "Net-(Q3-B)") (class "Default")
      (node (ref "Q3") (pin "2") (pinfunction "B_2") (pintype "unspecified"))
      (node (ref "R3") (pin "1") (pinfunction "1_1") (pintype "unspecified"))
    )
    (net (code "66") (name "Net-(Q4-B)") (class "Default")
      (node (ref "Q4") (pin "2") (pinfunction "B_2") (pintype "unspecified"))
      (node (ref "R4") (pin "1") (pinfunction "1_1") (pintype "unspecified"))
    )
    (net (code "67") (name "Net-(Q5-B)") (class "Default")
      (node (ref "Q5") (pin "2") (pinfunction "B_2") (pintype "unspecified"))
      (node (ref "R5") (pin "1") (pinfunction "1_1") (pintype "unspecified"))
    )
    (net (code "68") (name "Net-(Q6-B)") (class "Default")
      (node (ref "Q6") (pin "2") (pinfunction "B_2") (pintype "unspecified"))
      (node (ref "R6") (pin "1") (pinfunction "1_1") (pintype "unspecified"))
    )
    (net (code "69") (name "Net-(Q7-B)") (class "Default")
      (node (ref "Q7") (pin "2") (pinfunction "B_2") (pintype "unspecified"))
      (node (ref "R7") (pin "1") (pinfunction "1_1") (pintype "unspecified"))
    )
    (net (code "70") (name "Net-(Q8-B)") (class "Default")
      (node (ref "Q8") (pin "2") (pinfunction "B_2") (pintype "unspecified"))
      (node (ref "R8") (pin "1") (pinfunction "1_1") (pintype "unspecified"))
    )
    (net (code "71") (name "Net-(Q9-B)") (class "Default")
      (node (ref "Q9") (pin "2") (pinfunction "B_2") (pintype "unspecified"))
      (node (ref "R9") (pin "1") (pinfunction "1_1") (pintype "unspecified"))
    )
    (net (code "72") (name "Net-(Q10-B)") (class "Default")
      (node (ref "Q10") (pin "2") (pinfunction "B_2") (pintype "unspecified"))
      (node (ref "R10") (pin "1") (pinfunction "1_1") (pintype "unspecified"))
    )
    (net (code "73") (name "Net-(Q11-B)") (class "Default")
      (node (ref "Q11") (pin "2") (pinfunction "B_2") (pintype "unspecified"))
      (node (ref "R11") (pin "1") (pinfunction "1_1") (pintype "unspecified"))
    )
    (net (code "74") (name "Net-(Q12-B)") (class "Default")
      (node (ref "Q12") (pin "2") (pinfunction "B_2") (pintype "unspecified"))
      (node (ref "R12") (pin "1") (pinfunction "1_1") (pintype "unspecified"))
    )
    (net (code "75") (name "Net-(Q13-B)") (class "Default")
      (node (ref "Q13") (pin "2") (pinfunction "B_2") (pintype "unspecified"))
      (node (ref "R13") (pin "1") (pinfunction "1_1") (pintype "unspecified"))
    )
    (net (code "76") (name "Net-(Q14-B)") (class "Default")
      (node (ref "Q14") (pin "2") (pinfunction "B_2") (pintype "unspecified"))
      (node (ref "R14") (pin "1") (pinfunction "1_1") (pintype "unspecified"))
    )
    (net (code "77") (name "Net-(Q15-B)") (class "Default")
      (node (ref "Q15") (pin "2") (pinfunction "B_2") (pintype "unspecified"))
      (node (ref "R15") (pin "1") (pinfunction "1_1") (pintype "unspecified"))
    )
    (net (code "78") (name "Net-(Q16-B)") (class "Default")
      (node (ref "Q16") (pin "2") (pinfunction "B_2") (pintype "unspecified"))
      (node (ref "R16") (pin "1") (pinfunction "1_1") (pintype "unspecified"))
    )
    (net (code "79") (name "Net-(U1-PB6_XTAL1)") (class "Default")
      (node (ref "C1") (pin "2") (pinfunction "2_2") (pintype "unspecified"))
      (node (ref "U1") (pin "9") (pinfunction "PB6_XTAL1_9") (pintype "bidirectional"))
      (node (ref "X1") (pin "1") (pinfunction "1_1") (pintype "unspecified"))
    )
    (net (code "80") (name "Net-(U1-PB7_XTAL2)") (class "Default")
      (node (ref "C2") (pin "2") (pinfunction "2_2") (pintype "unspecified"))
      (node (ref "U1") (pin "10") (pinfunction "PB7_XTAL2_10") (pintype "bidirectional"))
      (node (ref "X1") (pin "2") (pinfunction "2_2") (pintype "unspecified"))
    )
    (net (code "81") (name "Net-(U1-PC6_RESET#)") (class "Default")
      (node (ref "KEY1") (pin "3") (pinfunction "3_3") (pintype "input"))
      (node (ref "KEY1") (pin "4") (pinfunction "4_4") (pintype "input"))
      (node (ref "R25") (pin "1") (pinfunction "1_1") (pintype "unspecified"))
      (node (ref "U1") (pin "1") (pinfunction "PC6_RESET#_1") (pintype "bidirectional"))
    )
    (net (code "82") (name "Net-(U1-PCINT5_PB5)") (class "Default")
      (node (ref "LD1") (pin "1") (pinfunction "1_1") (pintype "unspecified"))
      (node (ref "U1") (pin "19") (pinfunction "PCINT5_PB5_19") (pintype "bidirectional"))
    )
    (net (code "83") (name "SCL") (class "Default")
      (node (ref "J1") (pin "4") (pinfunction "4_4") (pintype "unspecified"))
      (node (ref "U1") (pin "28") (pinfunction "PC5_ADC5_28") (pintype "bidirectional"))
    )
    (net (code "84") (name "SDA") (class "Default")
      (node (ref "J1") (pin "2") (pinfunction "2_2") (pintype "unspecified"))
      (node (ref "U1") (pin "27") (pinfunction "PC4_ADC4_27") (pintype "bidirectional"))
    )
    (net (code "85") (name "channel1") (class "Default")
      (node (ref "R1") (pin "2") (pinfunction "2_2") (pintype "unspecified"))
      (node (ref "R2") (pin "2") (pinfunction "2_2") (pintype "unspecified"))
      (node (ref "U1") (pin "4") (pinfunction "INT0_PD2_4") (pintype "bidirectional"))
    )
    (net (code "86") (name "channel2") (class "Default")
      (node (ref "R3") (pin "2") (pinfunction "2_2") (pintype "unspecified"))
      (node (ref "R4") (pin "2") (pinfunction "2_2") (pintype "unspecified"))
      (node (ref "U1") (pin "5") (pinfunction "INT1_PD3_5") (pintype "bidirectional"))
    )
    (net (code "87") (name "channel3") (class "Default")
      (node (ref "R5") (pin "2") (pinfunction "2_2") (pintype "unspecified"))
      (node (ref "R6") (pin "2") (pinfunction "2_2") (pintype "unspecified"))
      (node (ref "U1") (pin "6") (pinfunction "T0_PD4_6") (pintype "bidirectional"))
    )
    (net (code "88") (name "channel4") (class "Default")
      (node (ref "R7") (pin "2") (pinfunction "2_2") (pintype "unspecified"))
      (node (ref "R8") (pin "2") (pinfunction "2_2") (pintype "unspecified"))
      (node (ref "U1") (pin "11") (pinfunction "T1_PD5_11") (pintype "bidirectional"))
    )
    (net (code "89") (name "channel5") (class "Default")
      (node (ref "R10") (pin "2") (pinfunction "2_2") (pintype "unspecified"))
      (node (ref "R9") (pin "2") (pinfunction "2_2") (pintype "unspecified"))
      (node (ref "U1") (pin "12") (pinfunction "AIN0_PD6_12") (pintype "bidirectional"))
    )
    (net (code "90") (name "channel6") (class "Default")
      (node (ref "R11") (pin "2") (pinfunction "2_2") (pintype "unspecified"))
      (node (ref "R12") (pin "2") (pinfunction "2_2") (pintype "unspecified"))
      (node (ref "U1") (pin "13") (pinfunction "AIN1_PD7_13") (pintype "bidirectional"))
    )
    (net (code "91") (name "channel7") (class "Default")
      (node (ref "R13") (pin "2") (pinfunction "2_2") (pintype "unspecified"))
      (node (ref "R14") (pin "2") (pinfunction "2_2") (pintype "unspecified"))
      (node (ref "U1") (pin "14") (pinfunction "PCINT0_PB0_14") (pintype "bidirectional"))
    )
    (net (code "92") (name "channel8") (class "Default")
      (node (ref "R15") (pin "2") (pinfunction "2_2") (pintype "unspecified"))
      (node (ref "R16") (pin "2") (pinfunction "2_2") (pintype "unspecified"))
      (node (ref "U1") (pin "15") (pinfunction "PCINT1__PB1_15") (pintype "bidirectional"))
    )
    (net (code "93") (name "line1") (class "Default")
      (node (ref "K1") (pin "6") (pinfunction "6_6") (pintype "unspecified"))
      (node (ref "K11") (pin "6") (pinfunction "6_6") (pintype "unspecified"))
      (node (ref "K13") (pin "6") (pinfunction "6_6") (pintype "unspecified"))
      (node (ref "K15") (pin "6") (pinfunction "6_6") (pintype "unspecified"))
      (node (ref "K3") (pin "6") (pinfunction "6_6") (pintype "unspecified"))
      (node (ref "K5") (pin "6") (pinfunction "6_6") (pintype "unspecified"))
      (node (ref "K7") (pin "6") (pinfunction "6_6") (pintype "unspecified"))
      (node (ref "K9") (pin "6") (pinfunction "6_6") (pintype "unspecified"))
      (node (ref "P18") (pin "1") (pinfunction "1_1") (pintype "input"))
    )
    (net (code "94") (name "line2") (class "Default")
      (node (ref "K10") (pin "6") (pinfunction "6_6") (pintype "unspecified"))
      (node (ref "K12") (pin "6") (pinfunction "6_6") (pintype "unspecified"))
      (node (ref "K14") (pin "6") (pinfunction "6_6") (pintype "unspecified"))
      (node (ref "K16") (pin "6") (pinfunction "6_6") (pintype "unspecified"))
      (node (ref "K2") (pin "6") (pinfunction "6_6") (pintype "unspecified"))
      (node (ref "K4") (pin "6") (pinfunction "6_6") (pintype "unspecified"))
      (node (ref "K6") (pin "6") (pinfunction "6_6") (pintype "unspecified"))
      (node (ref "K8") (pin "6") (pinfunction "6_6") (pintype "unspecified"))
      (node (ref "P18") (pin "2") (pinfunction "2_2") (pintype "input"))
    )
    (net (code "95") (name "unconnected-(K1-Pad7)") (class "Default")
      (node (ref "K1") (pin "7") (pinfunction "7_7") (pintype "unspecified+no_connect"))
    )
    (net (code "96") (name "unconnected-(K2-Pad7)") (class "Default")
      (node (ref "K2") (pin "7") (pinfunction "7_7") (pintype "unspecified+no_connect"))
    )
    (net (code "97") (name "unconnected-(K3-Pad7)") (class "Default")
      (node (ref "K3") (pin "7") (pinfunction "7_7") (pintype "unspecified+no_connect"))
    )
    (net (code "98") (name "unconnected-(K4-Pad7)") (class "Default")
      (node (ref "K4") (pin "7") (pinfunction "7_7") (pintype "unspecified+no_connect"))
    )
    (net (code "99") (name "unconnected-(K5-Pad7)") (class "Default")
      (node (ref "K5") (pin "7") (pinfunction "7_7") (pintype "unspecified+no_connect"))
    )
    (net (code "100") (name "unconnected-(K6-Pad7)") (class "Default")
      (node (ref "K6") (pin "7") (pinfunction "7_7") (pintype "unspecified+no_connect"))
    )
    (net (code "101") (name "unconnected-(K7-Pad7)") (class "Default")
      (node (ref "K7") (pin "7") (pinfunction "7_7") (pintype "unspecified+no_connect"))
    )
    (net (code "102") (name "unconnected-(K8-Pad7)") (class "Default")
      (node (ref "K8") (pin "7") (pinfunction "7_7") (pintype "unspecified+no_connect"))
    )
    (net (code "103") (name "unconnected-(K9-Pad7)") (class "Default")
      (node (ref "K9") (pin "7") (pinfunction "7_7") (pintype "unspecified+no_connect"))
    )
    (net (code "104") (name "unconnected-(K10-Pad7)") (class "Default")
      (node (ref "K10") (pin "7") (pinfunction "7_7") (pintype "unspecified+no_connect"))
    )
    (net (code "105") (name "unconnected-(K11-Pad7)") (class "Default")
      (node (ref "K11") (pin "7") (pinfunction "7_7") (pintype "unspecified+no_connect"))
    )
    (net (code "106") (name "unconnected-(K12-Pad7)") (class "Default")
      (node (ref "K12") (pin "7") (pinfunction "7_7") (pintype "unspecified+no_connect"))
    )
    (net (code "107") (name "unconnected-(K13-Pad7)") (class "Default")
      (node (ref "K13") (pin "7") (pinfunction "7_7") (pintype "unspecified+no_connect"))
    )
    (net (code "108") (name "unconnected-(K14-Pad7)") (class "Default")
      (node (ref "K14") (pin "7") (pinfunction "7_7") (pintype "unspecified+no_connect"))
    )
    (net (code "109") (name "unconnected-(K15-Pad7)") (class "Default")
      (node (ref "K15") (pin "7") (pinfunction "7_7") (pintype "unspecified+no_connect"))
    )
    (net (code "110") (name "unconnected-(K16-Pad7)") (class "Default")
      (node (ref "K16") (pin "7") (pinfunction "7_7") (pintype "unspecified+no_connect"))
    )
    (net (code "111") (name "unconnected-(U1-AREF-Pad21)") (class "Default")
      (node (ref "U1") (pin "21") (pinfunction "AREF_21") (pintype "passive+no_connect"))
    )
    (net (code "112") (name "unconnected-(U1-PD0_RXD-Pad2)") (class "Default")
      (node (ref "U1") (pin "2") (pinfunction "PD0_RXD_2") (pintype "bidirectional+no_connect"))
    )
    (net (code "113") (name "unconnected-(U1-PD1_TXD-Pad3)") (class "Default")
      (node (ref "U1") (pin "3") (pinfunction "PD1_TXD_3") (pintype "bidirectional+no_connect"))
    )
  )
)
